# 505153_1_3.net
KiCad netlist of a schematic drawn in Altium Designer
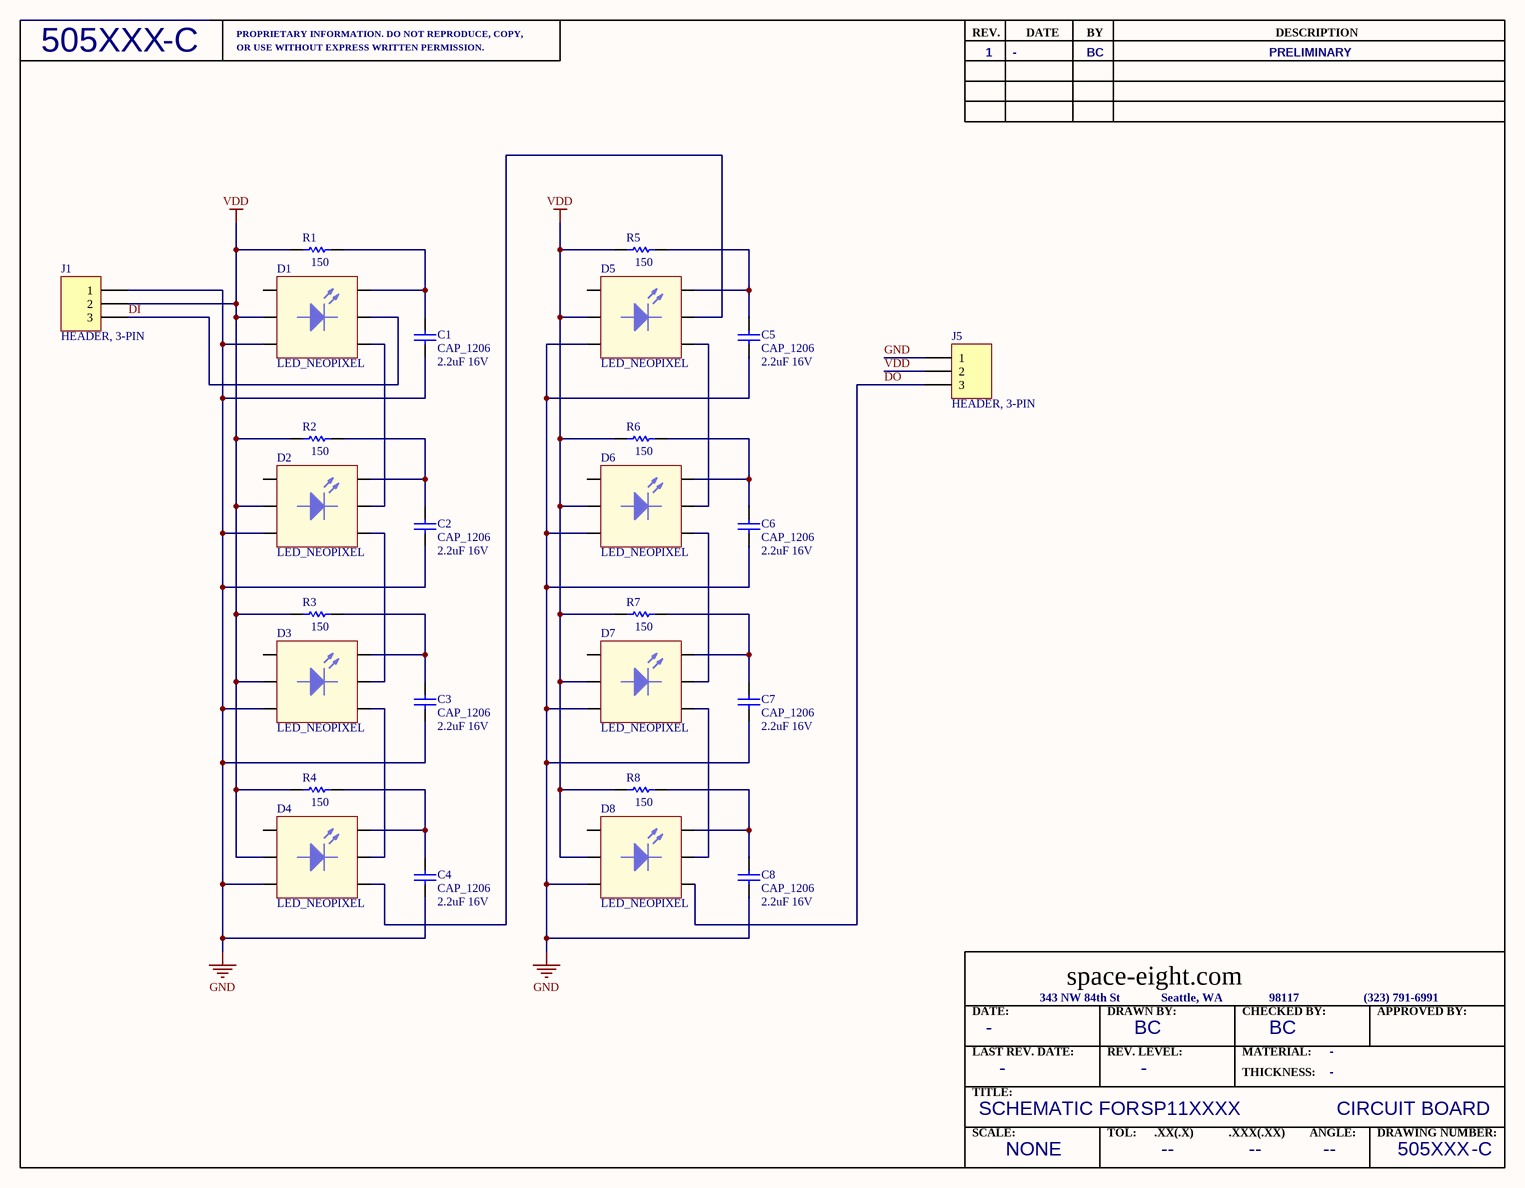
[diagram p0: 505153_1_3.SchDoc]

(export (version "E")
  (design (tool "Eeschema 10.0.6"))
  (components
    (comp (ref "C1")
      (value "CAP_1206")
      (footprint "SMT_1206_MOD")
      (description "CAP")
      (fields
        (field (name "MANUFACTURER") "Generic Components")
        (field (name "ALTIUM_VALUE") "2.2uF 16V")
        (field (name "PUBLISHER") "Altium Limited")
      )
      (libsource (lib "Custom_Lib_2") (part "CAP_1206"))
    )
    (comp (ref "C2")
      (value "CAP_1206")
      (footprint "SMT_1206_MOD")
      (description "CAP")
      (fields
        (field (name "MANUFACTURER") "Generic Components")
        (field (name "ALTIUM_VALUE") "2.2uF 16V")
        (field (name "PUBLISHER") "Altium Limited")
      )
      (libsource (lib "Custom_Lib_2") (part "CAP_1206"))
    )
    (comp (ref "C3")
      (value "CAP_1206")
      (footprint "SMT_1206_MOD")
      (description "CAP")
      (fields
        (field (name "MANUFACTURER") "Generic Components")
        (field (name "ALTIUM_VALUE") "2.2uF 16V")
        (field (name "PUBLISHER") "Altium Limited")
      )
      (libsource (lib "Custom_Lib_2") (part "CAP_1206"))
    )
    (comp (ref "C4")
      (value "CAP_1206")
      (footprint "SMT_1206_MOD")
      (description "CAP")
      (fields
        (field (name "MANUFACTURER") "Generic Components")
        (field (name "ALTIUM_VALUE") "2.2uF 16V")
        (field (name "PUBLISHER") "Altium Limited")
      )
      (libsource (lib "Custom_Lib_2") (part "CAP_1206"))
    )
    (comp (ref "C5")
      (value "CAP_1206")
      (footprint "SMT_1206_MOD")
      (description "CAP")
      (fields
        (field (name "MANUFACTURER") "Generic Components")
        (field (name "ALTIUM_VALUE") "2.2uF 16V")
        (field (name "PUBLISHER") "Altium Limited")
      )
      (libsource (lib "Custom_Lib_2") (part "CAP_1206"))
    )
    (comp (ref "C6")
      (value "CAP_1206")
      (footprint "SMT_1206_MOD")
      (description "CAP")
      (fields
        (field (name "MANUFACTURER") "Generic Components")
        (field (name "ALTIUM_VALUE") "2.2uF 16V")
        (field (name "PUBLISHER") "Altium Limited")
      )
      (libsource (lib "Custom_Lib_2") (part "CAP_1206"))
    )
    (comp (ref "C7")
      (value "CAP_1206")
      (footprint "SMT_1206_MOD")
      (description "CAP")
      (fields
        (field (name "MANUFACTURER") "Generic Components")
        (field (name "ALTIUM_VALUE") "2.2uF 16V")
        (field (name "PUBLISHER") "Altium Limited")
      )
      (libsource (lib "Custom_Lib_2") (part "CAP_1206"))
    )
    (comp (ref "C8")
      (value "CAP_1206")
      (footprint "SMT_1206_MOD")
      (description "CAP")
      (fields
        (field (name "MANUFACTURER") "Generic Components")
        (field (name "ALTIUM_VALUE") "2.2uF 16V")
        (field (name "PUBLISHER") "Altium Limited")
      )
      (libsource (lib "Custom_Lib_2") (part "CAP_1206"))
    )
    (comp (ref "D1")
      (value "LED_NEOPIXEL")
      (footprint "NEOPIXEL")
      (description "RGB NEOPIXEL")
      (fields (field (name "MANUFACTURER") "Generic Components") (field (name "PUBLISHER") "Altium Limited"))
      (libsource (lib "Custom_Lib_2") (part "LED_NEOPIXEL"))
    )
    (comp (ref "D2")
      (value "LED_NEOPIXEL")
      (footprint "NEOPIXEL")
      (description "RGB NEOPIXEL")
      (fields (field (name "MANUFACTURER") "Generic Components") (field (name "PUBLISHER") "Altium Limited"))
      (libsource (lib "Custom_Lib_2") (part "LED_NEOPIXEL"))
    )
    (comp (ref "D3")
      (value "LED_NEOPIXEL")
      (footprint "NEOPIXEL")
      (description "RGB NEOPIXEL")
      (fields (field (name "MANUFACTURER") "Generic Components") (field (name "PUBLISHER") "Altium Limited"))
      (libsource (lib "Custom_Lib_2") (part "LED_NEOPIXEL"))
    )
    (comp (ref "D4")
      (value "LED_NEOPIXEL")
      (footprint "NEOPIXEL")
      (description "RGB NEOPIXEL")
      (fields (field (name "MANUFACTURER") "Generic Components") (field (name "PUBLISHER") "Altium Limited"))
      (libsource (lib "Custom_Lib_2") (part "LED_NEOPIXEL"))
    )
    (comp (ref "D5")
      (value "LED_NEOPIXEL")
      (footprint "NEOPIXEL")
      (description "RGB NEOPIXEL")
      (fields (field (name "MANUFACTURER") "Generic Components") (field (name "PUBLISHER") "Altium Limited"))
      (libsource (lib "Custom_Lib_2") (part "LED_NEOPIXEL"))
    )
    (comp (ref "D6")
      (value "LED_NEOPIXEL")
      (footprint "NEOPIXEL")
      (description "RGB NEOPIXEL")
      (fields (field (name "MANUFACTURER") "Generic Components") (field (name "PUBLISHER") "Altium Limited"))
      (libsource (lib "Custom_Lib_2") (part "LED_NEOPIXEL"))
    )
    (comp (ref "D7")
      (value "LED_NEOPIXEL")
      (footprint "NEOPIXEL")
      (description "RGB NEOPIXEL")
      (fields (field (name "MANUFACTURER") "Generic Components") (field (name "PUBLISHER") "Altium Limited"))
      (libsource (lib "Custom_Lib_2") (part "LED_NEOPIXEL"))
    )
    (comp (ref "D8")
      (value "LED_NEOPIXEL")
      (footprint "NEOPIXEL")
      (description "RGB NEOPIXEL")
      (fields (field (name "MANUFACTURER") "Generic Components") (field (name "PUBLISHER") "Altium Limited"))
      (libsource (lib "Custom_Lib_2") (part "LED_NEOPIXEL"))
    )
    (comp (ref "J1")
      (value "HEADER, 3-PIN")
      (footprint "HEADER, 3-pin")
      (description "Header, 3-Pin")
      (fields (field (name "PUBLISHER") "Altium Limited"))
      (libsource (lib "") (part "HEADER, 3-PIN_1_1"))
    )
    (comp (ref "J5")
      (value "HEADER, 3-PIN")
      (footprint "HEADER, 3-pin")
      (description "Header, 3-Pin")
      (fields (field (name "PUBLISHER") "Altium Limited"))
      (libsource (lib "Custom_Lib_2") (part "HEADER, 3-PIN_1"))
    )
    (comp (ref "R1")
      (value "150")
      (footprint "SMT_1206_MOD")
      (description "RES")
      (fields
        (field (name "MANUFACTURER") "Generic Components")
        (field (name "Comment") "RES_1206")
        (field (name "PUBLISHER") "Altium Limited")
      )
      (libsource (lib "Custom_Lib_2") (part "RES_1206"))
    )
    (comp (ref "R2")
      (value "150")
      (footprint "SMT_1206_MOD")
      (description "RES")
      (fields
        (field (name "MANUFACTURER") "Generic Components")
        (field (name "Comment") "RES_1206")
        (field (name "PUBLISHER") "Altium Limited")
      )
      (libsource (lib "Custom_Lib_2") (part "RES_1206"))
    )
    (comp (ref "R3")
      (value "150")
      (footprint "SMT_1206_MOD")
      (description "RES")
      (fields
        (field (name "MANUFACTURER") "Generic Components")
        (field (name "Comment") "RES_1206")
        (field (name "PUBLISHER") "Altium Limited")
      )
      (libsource (lib "Custom_Lib_2") (part "RES_1206"))
    )
    (comp (ref "R4")
      (value "150")
      (footprint "SMT_1206_MOD")
      (description "RES")
      (fields
        (field (name "MANUFACTURER") "Generic Components")
        (field (name "Comment") "RES_1206")
        (field (name "PUBLISHER") "Altium Limited")
      )
      (libsource (lib "Custom_Lib_2") (part "RES_1206"))
    )
    (comp (ref "R5")
      (value "150")
      (footprint "SMT_1206_MOD")
      (description "RES")
      (fields
        (field (name "MANUFACTURER") "Generic Components")
        (field (name "Comment") "RES_1206")
        (field (name "PUBLISHER") "Altium Limited")
      )
      (libsource (lib "Custom_Lib_2") (part "RES_1206"))
    )
    (comp (ref "R6")
      (value "150")
      (footprint "SMT_1206_MOD")
      (description "RES")
      (fields
        (field (name "MANUFACTURER") "Generic Components")
        (field (name "Comment") "RES_1206")
        (field (name "PUBLISHER") "Altium Limited")
      )
      (libsource (lib "Custom_Lib_2") (part "RES_1206"))
    )
    (comp (ref "R7")
      (value "150")
      (footprint "SMT_1206_MOD")
      (description "RES")
      (fields
        (field (name "MANUFACTURER") "Generic Components")
        (field (name "Comment") "RES_1206")
        (field (name "PUBLISHER") "Altium Limited")
      )
      (libsource (lib "Custom_Lib_2") (part "RES_1206"))
    )
    (comp (ref "R8")
      (value "150")
      (footprint "SMT_1206_MOD")
      (description "RES")
      (fields
        (field (name "MANUFACTURER") "Generic Components")
        (field (name "Comment") "RES_1206")
        (field (name "PUBLISHER") "Altium Limited")
      )
      (libsource (lib "Custom_Lib_2") (part "RES_1206"))
    )
  )
  (nets
    (net (code "1") (name "/DI") (class "Default")
      (node (ref "D1") (pin "2") (pinfunction "DI_2") (pintype "passive"))
      (node (ref "J1") (pin "3") (pinfunction "3_3") (pintype "passive"))
    )
    (net (code "2") (name "/DO") (class "Default")
      (node (ref "D8") (pin "1") (pinfunction "DO_1") (pintype "passive"))
      (node (ref "J5") (pin "3") (pinfunction "3_3") (pintype "passive"))
    )
    (net (code "3") (name "GND") (class "Default")
      (node (ref "C1") (pin "1") (pinfunction "1_1") (pintype "passive"))
      (node (ref "C2") (pin "1") (pinfunction "1_1") (pintype "passive"))
      (node (ref "C3") (pin "1") (pinfunction "1_1") (pintype "passive"))
      (node (ref "C4") (pin "1") (pinfunction "1_1") (pintype "passive"))
      (node (ref "C5") (pin "1") (pinfunction "1_1") (pintype "passive"))
      (node (ref "C6") (pin "1") (pinfunction "1_1") (pintype "passive"))
      (node (ref "C7") (pin "1") (pinfunction "1_1") (pintype "passive"))
      (node (ref "C8") (pin "1") (pinfunction "1_1") (pintype "passive"))
      (node (ref "D1") (pin "6") (pinfunction "VSS_6") (pintype "passive"))
      (node (ref "D2") (pin "6") (pinfunction "VSS_6") (pintype "passive"))
      (node (ref "D3") (pin "6") (pinfunction "VSS_6") (pintype "passive"))
      (node (ref "D4") (pin "6") (pinfunction "VSS_6") (pintype "passive"))
      (node (ref "D5") (pin "6") (pinfunction "VSS_6") (pintype "passive"))
      (node (ref "D6") (pin "6") (pinfunction "VSS_6") (pintype "passive"))
      (node (ref "D7") (pin "6") (pinfunction "VSS_6") (pintype "passive"))
      (node (ref "D8") (pin "6") (pinfunction "VSS_6") (pintype "passive"))
      (node (ref "J1") (pin "1") (pinfunction "1_1") (pintype "passive"))
      (node (ref "J5") (pin "1") (pinfunction "1_1") (pintype "passive"))
    )
    (net (code "4") (name "Net-(D1-DO)") (class "Default")
      (node (ref "D1") (pin "1") (pinfunction "DO_1") (pintype "passive"))
      (node (ref "D2") (pin "2") (pinfunction "DI_2") (pintype "passive"))
    )
    (net (code "5") (name "Net-(D1-VCC)") (class "Default")
      (node (ref "C1") (pin "2") (pinfunction "2_2") (pintype "passive"))
      (node (ref "D1") (pin "3") (pinfunction "VCC_3") (pintype "passive"))
      (node (ref "R1") (pin "2") (pinfunction "2_2") (pintype "passive"))
    )
    (net (code "6") (name "Net-(D2-DO)") (class "Default")
      (node (ref "D2") (pin "1") (pinfunction "DO_1") (pintype "passive"))
      (node (ref "D3") (pin "2") (pinfunction "DI_2") (pintype "passive"))
    )
    (net (code "7") (name "Net-(D2-VCC)") (class "Default")
      (node (ref "C2") (pin "2") (pinfunction "2_2") (pintype "passive"))
      (node (ref "D2") (pin "3") (pinfunction "VCC_3") (pintype "passive"))
      (node (ref "R2") (pin "2") (pinfunction "2_2") (pintype "passive"))
    )
    (net (code "8") (name "Net-(D3-DO)") (class "Default")
      (node (ref "D3") (pin "1") (pinfunction "DO_1") (pintype "passive"))
      (node (ref "D4") (pin "2") (pinfunction "DI_2") (pintype "passive"))
    )
    (net (code "9") (name "Net-(D3-VCC)") (class "Default")
      (node (ref "C3") (pin "2") (pinfunction "2_2") (pintype "passive"))
      (node (ref "D3") (pin "3") (pinfunction "VCC_3") (pintype "passive"))
      (node (ref "R3") (pin "2") (pinfunction "2_2") (pintype "passive"))
    )
    (net (code "10") (name "Net-(D4-DO)") (class "Default")
      (node (ref "D4") (pin "1") (pinfunction "DO_1") (pintype "passive"))
      (node (ref "D5") (pin "2") (pinfunction "DI_2") (pintype "passive"))
    )
    (net (code "11") (name "Net-(D4-VCC)") (class "Default")
      (node (ref "C4") (pin "2") (pinfunction "2_2") (pintype "passive"))
      (node (ref "D4") (pin "3") (pinfunction "VCC_3") (pintype "passive"))
      (node (ref "R4") (pin "2") (pinfunction "2_2") (pintype "passive"))
    )
    (net (code "12") (name "Net-(D5-DO)") (class "Default")
      (node (ref "D5") (pin "1") (pinfunction "DO_1") (pintype "passive"))
      (node (ref "D6") (pin "2") (pinfunction "DI_2") (pintype "passive"))
    )
    (net (code "13") (name "Net-(D5-VCC)") (class "Default")
      (node (ref "C5") (pin "2") (pinfunction "2_2") (pintype "passive"))
      (node (ref "D5") (pin "3") (pinfunction "VCC_3") (pintype "passive"))
      (node (ref "R5") (pin "2") (pinfunction "2_2") (pintype "passive"))
    )
    (net (code "14") (name "Net-(D6-DO)") (class "Default")
      (node (ref "D6") (pin "1") (pinfunction "DO_1") (pintype "passive"))
      (node (ref "D7") (pin "2") (pinfunction "DI_2") (pintype "passive"))
    )
    (net (code "15") (name "Net-(D6-VCC)") (class "Default")
      (node (ref "C6") (pin "2") (pinfunction "2_2") (pintype "passive"))
      (node (ref "D6") (pin "3") (pinfunction "VCC_3") (pintype "passive"))
      (node (ref "R6") (pin "2") (pinfunction "2_2") (pintype "passive"))
    )
    (net (code "16") (name "Net-(D7-DO)") (class "Default")
      (node (ref "D7") (pin "1") (pinfunction "DO_1") (pintype "passive"))
      (node (ref "D8") (pin "2") (pinfunction "DI_2") (pintype "passive"))
    )
    (net (code "17") (name "Net-(D7-VCC)") (class "Default")
      (node (ref "C7") (pin "2") (pinfunction "2_2") (pintype "passive"))
      (node (ref "D7") (pin "3") (pinfunction "VCC_3") (pintype "passive"))
      (node (ref "R7") (pin "2") (pinfunction "2_2") (pintype "passive"))
    )
    (net (code "18") (name "Net-(D8-VCC)") (class "Default")
      (node (ref "C8") (pin "2") (pinfunction "2_2") (pintype "passive"))
      (node (ref "D8") (pin "3") (pinfunction "VCC_3") (pintype "passive"))
      (node (ref "R8") (pin "2") (pinfunction "2_2") (pintype "passive"))
    )
    (net (code "19") (name "VDD") (class "Default")
      (node (ref "D1") (pin "5") (pinfunction "VDD_5") (pintype "passive"))
      (node (ref "D2") (pin "5") (pinfunction "VDD_5") (pintype "passive"))
      (node (ref "D3") (pin "5") (pinfunction "VDD_5") (pintype "passive"))
      (node (ref "D4") (pin "5") (pinfunction "VDD_5") (pintype "passive"))
      (node (ref "D5") (pin "5") (pinfunction "VDD_5") (pintype "passive"))
      (node (ref "D6") (pin "5") (pinfunction "VDD_5") (pintype "passive"))
      (node (ref "D7") (pin "5") (pinfunction "VDD_5") (pintype "passive"))
      (node (ref "D8") (pin "5") (pinfunction "VDD_5") (pintype "passive"))
      (node (ref "J1") (pin "2") (pinfunction "2_2") (pintype "passive"))
      (node (ref "J5") (pin "2") (pinfunction "2_2") (pintype "passive"))
      (node (ref "R1") (pin "1") (pinfunction "1_1") (pintype "passive"))
      (node (ref "R2") (pin "1") (pinfunction "1_1") (pintype "passive"))
      (node (ref "R3") (pin "1") (pinfunction "1_1") (pintype "passive"))
      (node (ref "R4") (pin "1") (pinfunction "1_1") (pintype "passive"))
      (node (ref "R5") (pin "1") (pinfunction "1_1") (pintype "passive"))
      (node (ref "R6") (pin "1") (pinfunction "1_1") (pintype "passive"))
      (node (ref "R7") (pin "1") (pinfunction "1_1") (pintype "passive"))
      (node (ref "R8") (pin "1") (pinfunction "1_1") (pintype "passive"))
    )
    (net (code "20") (name "unconnected-(D1-NC-Pad4)") (class "Default")
      (node (ref "D1") (pin "4") (pinfunction "NC_4") (pintype "passive"))
    )
    (net (code "21") (name "unconnected-(D2-NC-Pad4)") (class "Default")
      (node (ref "D2") (pin "4") (pinfunction "NC_4") (pintype "passive"))
    )
    (net (code "22") (name "unconnected-(D3-NC-Pad4)") (class "Default")
      (node (ref "D3") (pin "4") (pinfunction "NC_4") (pintype "passive"))
    )
    (net (code "23") (name "unconnected-(D4-NC-Pad4)") (class "Default")
      (node (ref "D4") (pin "4") (pinfunction "NC_4") (pintype "passive"))
    )
    (net (code "24") (name "unconnected-(D5-NC-Pad4)") (class "Default")
      (node (ref "D5") (pin "4") (pinfunction "NC_4") (pintype "passive"))
    )
    (net (code "25") (name "unconnected-(D6-NC-Pad4)") (class "Default")
      (node (ref "D6") (pin "4") (pinfunction "NC_4") (pintype "passive"))
    )
    (net (code "26") (name "unconnected-(D7-NC-Pad4)") (class "Default")
      (node (ref "D7") (pin "4") (pinfunction "NC_4") (pintype "passive"))
    )
    (net (code "27") (name "unconnected-(D8-NC-Pad4)") (class "Default")
      (node (ref "D8") (pin "4") (pinfunction "NC_4") (pintype "passive"))
    )
  )
)
